# BB.net
KiCad netlist of a schematic drawn in Altium Designer
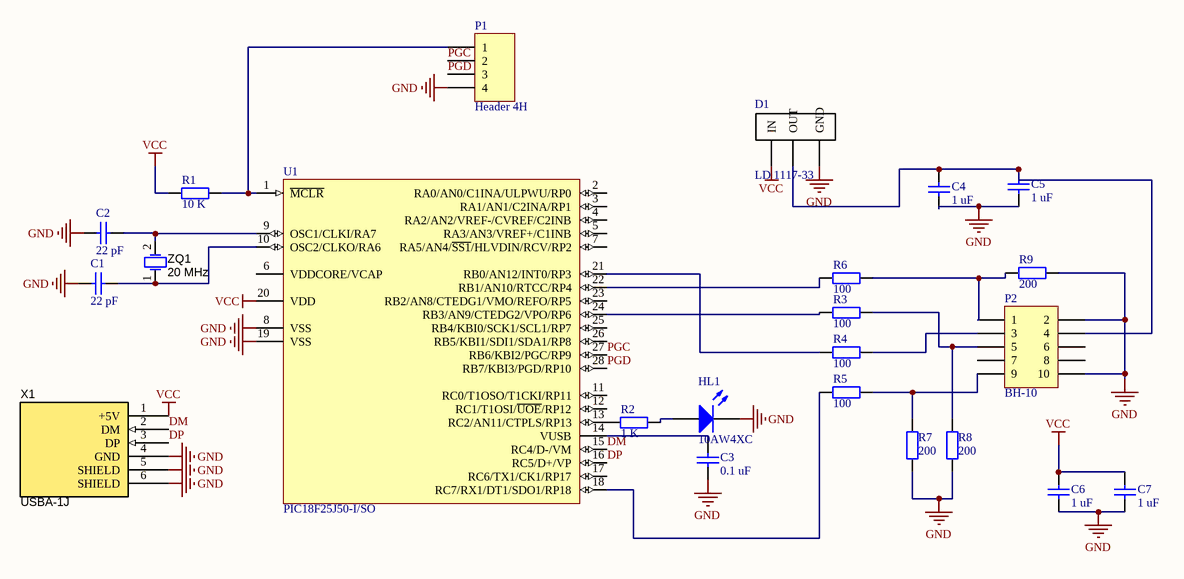
[diagram p0: BB.SchDoc]

(export (version "E")
  (design (tool "Eeschema 10.0.6"))
  (components
    (comp (ref "C1")
      (value "22 pF")
      (footprint "C0805")
      (description "Capacitor (Semiconductor SIM Model)")
      (fields (field (name "Comment") "Cap Semi_2") (field (name "PUBLISHER") "Sergeev"))
      (libsource (lib "Sergeev_altium_2012.03.10") (part "Cap Semi_2"))
    )
    (comp (ref "C2")
      (value "22 pF")
      (footprint "C0805")
      (description "Capacitor (Semiconductor SIM Model)")
      (fields (field (name "Comment") "Cap Semi_2") (field (name "PUBLISHER") "Sergeev"))
      (libsource (lib "Sergeev_altium_2012.03.10") (part "Cap Semi_2"))
    )
    (comp (ref "C3")
      (value "0.1 uF")
      (footprint "C0805")
      (description "Capacitor (Semiconductor SIM Model)")
      (fields (field (name "Comment") "Cap Semi_2") (field (name "PUBLISHER") "Sergeev"))
      (libsource (lib "Sergeev_altium_2012.03.10") (part "Cap Semi_2"))
    )
    (comp (ref "C4")
      (value "1 uF")
      (footprint "C0805")
      (description "Capacitor (Semiconductor SIM Model)")
      (fields (field (name "Comment") "Cap Semi_2") (field (name "PUBLISHER") "Sergeev"))
      (libsource (lib "Sergeev_altium_2012.03.10") (part "Cap Semi_2"))
    )
    (comp (ref "C5")
      (value "1 uF")
      (footprint "C0805")
      (description "Capacitor (Semiconductor SIM Model)")
      (fields (field (name "Comment") "Cap Semi_2") (field (name "PUBLISHER") "Sergeev"))
      (libsource (lib "Sergeev_altium_2012.03.10") (part "Cap Semi_2"))
    )
    (comp (ref "C6")
      (value "1 uF")
      (footprint "C0805")
      (description "Capacitor (Semiconductor SIM Model)")
      (fields (field (name "Comment") "Cap Semi_2") (field (name "PUBLISHER") "Sergeev"))
      (libsource (lib "Sergeev_altium_2012.03.10") (part "Cap Semi_2"))
    )
    (comp (ref "C7")
      (value "1 uF")
      (footprint "C0805")
      (description "Capacitor (Semiconductor SIM Model)")
      (fields (field (name "Comment") "Cap Semi_2") (field (name "PUBLISHER") "Sergeev"))
      (libsource (lib "Sergeev_altium_2012.03.10") (part "Cap Semi_2"))
    )
    (comp (ref "D1")
      (value "LD 1117-33")
      (footprint "SOT230P700X180-4N")
      (libsource (lib "BB") (part "LD 1117-33"))
    )
    (comp (ref "HL1")
      (value "10AW4XC")
      (footprint "Led_Rus D=10 d=0.9 w=2.54")
      (description "Typical INFRARED GaAs LED")
      (fields (field (name "PUBLISHER") "Сергеев"))
      (libsource (lib "Sergeev_altium_2012.03.10") (part "LED D=10"))
    )
    (comp (ref "P1")
      (value "Header 4H")
      (footprint "HDR1X4H")
      (description "Header, 4-Pin, Right Angle")
      (fields (field (name "PUBLISHER") "Altium Limited"))
      (libsource (lib "Miscellaneous Connectors") (part "Header 4H"))
    )
    (comp (ref "P2")
      (value "BH-10")
      (footprint "BH-10 HDR2X5")
      (description "Header, 5-Pin, Dual row 2.54")
      (fields (field (name "PUBLISHER") "Altium Limited"))
      (libsource (lib "Sergeev_altium_2012.03.10") (part "BH-10"))
    )
    (comp (ref "R1")
      (value "10 K")
      (footprint "2012[0805] - wa")
      (fields (field (name "Comment") "Resistor 0805"))
      (libsource (lib "Sergeev_altium_2012.03.10") (part "Resistor 0805"))
    )
    (comp (ref "R2")
      (value "1 K")
      (footprint "2012[0805] - wa")
      (fields (field (name "Comment") "Resistor 0805"))
      (libsource (lib "") (part "Resistor 0805_2"))
    )
    (comp (ref "R3")
      (value "100")
      (footprint "2012[0805] - wa")
      (fields (field (name "Comment") "Resistor 0805"))
      (libsource (lib "Sergeev_altium_2012.03.10") (part "Resistor 0805"))
    )
    (comp (ref "R4")
      (value "100")
      (footprint "2012[0805] - wa")
      (fields (field (name "Comment") "Resistor 0805"))
      (libsource (lib "Sergeev_altium_2012.03.10") (part "Resistor 0805"))
    )
    (comp (ref "R5")
      (value "100")
      (footprint "2012[0805] - wa")
      (fields (field (name "Comment") "Resistor 0805"))
      (libsource (lib "Sergeev_altium_2012.03.10") (part "Resistor 0805"))
    )
    (comp (ref "R6")
      (value "100")
      (footprint "2012[0805] - wa")
      (fields (field (name "Comment") "Resistor 0805"))
      (libsource (lib "Sergeev_altium_2012.03.10") (part "Resistor 0805"))
    )
    (comp (ref "R7")
      (value "200")
      (footprint "2012[0805] - wa")
      (fields (field (name "Comment") "Resistor 0805"))
      (libsource (lib "") (part "Resistor 0805_1"))
    )
    (comp (ref "R8")
      (value "200")
      (footprint "2012[0805] - wa")
      (fields (field (name "Comment") "Resistor 0805"))
      (libsource (lib "") (part "Resistor 0805_1"))
    )
    (comp (ref "R9")
      (value "200")
      (footprint "2012[0805] - wa")
      (fields (field (name "Comment") "Resistor 0805"))
      (libsource (lib "Sergeev_altium_2012.03.10") (part "Resistor 0805"))
    )
    (comp (ref "U1")
      (value "PIC18F25J50-I/SO")
      (footprint "SOIC-SO28_N")
      (fields (field (name "PUBLISHER") "Altium Limited"))
      (libsource (lib "Microchip Microcontroller 8-Bit PIC18") (part "PIC18F25J50-I/SO"))
    )
    (comp (ref "X1")
      (value "USBA-1J")
      (footprint "USB2.5-2H4C")
      (description "Разъем USBA на плату")
      (libsource (lib "Sergeev_altium_2012.03.10") (part "USBA-1J"))
    )
    (comp (ref "ZQ1")
      (value "20 MHz")
      (footprint "HC49S")
      (description "Crystal Oscillator")
      (fields (field (name "PUBLISHER") "Altium Limited"))
      (libsource (lib "Sergeev_altium_2012.03.10") (part "XTAL"))
    )
  )
  (nets
    (net (code "1") (name "/DM") (class "Default")
      (node (ref "U1") (pin "15") (pinfunction "RC4/D-/VM_15") (pintype "bidirectional"))
      (node (ref "X1") (pin "2") (pinfunction "DM_2") (pintype "input"))
    )
    (net (code "2") (name "/DP") (class "Default")
      (node (ref "U1") (pin "16") (pinfunction "RC5/D+/VP_16") (pintype "bidirectional"))
      (node (ref "X1") (pin "3") (pinfunction "DP_3") (pintype "input"))
    )
    (net (code "3") (name "/PGC") (class "Default")
      (node (ref "P1") (pin "2") (pinfunction "2_2") (pintype "passive"))
      (node (ref "U1") (pin "27") (pinfunction "RB6/KBI2/PGC/RP9_27") (pintype "bidirectional"))
    )
    (net (code "4") (name "/PGD") (class "Default")
      (node (ref "P1") (pin "3") (pinfunction "3_3") (pintype "passive"))
      (node (ref "U1") (pin "28") (pinfunction "RB7/KBI3/PGD/RP10_28") (pintype "bidirectional"))
    )
    (net (code "5") (name "GND") (class "Default")
      (node (ref "C1") (pin "2") (pinfunction "2_2") (pintype "passive"))
      (node (ref "C2") (pin "2") (pinfunction "2_2") (pintype "passive"))
      (node (ref "C3") (pin "1") (pinfunction "1_1") (pintype "passive"))
      (node (ref "C4") (pin "1") (pinfunction "1_1") (pintype "passive"))
      (node (ref "C5") (pin "1") (pinfunction "1_1") (pintype "passive"))
      (node (ref "C6") (pin "1") (pinfunction "1_1") (pintype "passive"))
      (node (ref "C7") (pin "1") (pinfunction "1_1") (pintype "passive"))
      (node (ref "D1") (pin "GND") (pinfunction "GND_GND") (pintype "passive"))
      (node (ref "HL1") (pin "2") (pinfunction "K_2") (pintype "passive"))
      (node (ref "P1") (pin "4") (pinfunction "4_4") (pintype "passive"))
      (node (ref "P2") (pin "10") (pinfunction "10_10") (pintype "passive"))
      (node (ref "P2") (pin "2") (pinfunction "2_2") (pintype "passive"))
      (node (ref "R7") (pin "1") (pinfunction "1_1") (pintype "passive"))
      (node (ref "R8") (pin "1") (pinfunction "1_1") (pintype "passive"))
      (node (ref "R9") (pin "2") (pinfunction "2_2") (pintype "passive"))
      (node (ref "U1") (pin "19") (pinfunction "VSS_19") (pintype "power_in"))
      (node (ref "U1") (pin "8") (pinfunction "VSS_8") (pintype "power_in"))
      (node (ref "X1") (pin "4") (pinfunction "GND_4") (pintype "power_in"))
      (node (ref "X1") (pin "5") (pinfunction "SHIELD_5") (pintype "power_in"))
      (node (ref "X1") (pin "6") (pinfunction "SHIELD_6") (pintype "power_in"))
    )
    (net (code "6") (name "Net-(C4-Pad2)") (class "Default")
      (node (ref "C4") (pin "2") (pinfunction "2_2") (pintype "passive"))
      (node (ref "C5") (pin "2") (pinfunction "2_2") (pintype "passive"))
      (node (ref "D1") (pin "OUT") (pinfunction "OUT_OUT") (pintype "passive"))
      (node (ref "P2") (pin "4") (pinfunction "4_4") (pintype "passive"))
    )
    (net (code "7") (name "Net-(HL1-A)") (class "Default")
      (node (ref "HL1") (pin "1") (pinfunction "A_1") (pintype "passive"))
      (node (ref "R2") (pin "1") (pinfunction "1_1") (pintype "passive"))
    )
    (net (code "8") (name "Net-(P2-Pad1)") (class "Default")
      (node (ref "P2") (pin "1") (pinfunction "1_1") (pintype "passive"))
      (node (ref "R6") (pin "2") (pinfunction "2_2") (pintype "passive"))
      (node (ref "R9") (pin "1") (pinfunction "1_1") (pintype "passive"))
    )
    (net (code "9") (name "Net-(P2-Pad3)") (class "Default")
      (node (ref "P2") (pin "3") (pinfunction "3_3") (pintype "passive"))
      (node (ref "R4") (pin "2") (pinfunction "2_2") (pintype "passive"))
    )
    (net (code "10") (name "Net-(P2-Pad5)") (class "Default")
      (node (ref "P2") (pin "5") (pinfunction "5_5") (pintype "passive"))
      (node (ref "R3") (pin "2") (pinfunction "2_2") (pintype "passive"))
      (node (ref "R8") (pin "2") (pinfunction "2_2") (pintype "passive"))
    )
    (net (code "11") (name "Net-(P2-Pad9)") (class "Default")
      (node (ref "P2") (pin "9") (pinfunction "9_9") (pintype "passive"))
      (node (ref "R5") (pin "2") (pinfunction "2_2") (pintype "passive"))
      (node (ref "R7") (pin "2") (pinfunction "2_2") (pintype "passive"))
    )
    (net (code "12") (name "Net-(U1-OSC1{slash}CLKI{slash}RA7)") (class "Default")
      (node (ref "C2") (pin "1") (pinfunction "1_1") (pintype "passive"))
      (node (ref "U1") (pin "9") (pinfunction "OSC1/CLKI/RA7_9") (pintype "bidirectional"))
      (node (ref "ZQ1") (pin "2") (pinfunction "OSC2_2") (pintype "passive"))
    )
    (net (code "13") (name "Net-(U1-OSC2{slash}CLKO{slash}RA6)") (class "Default")
      (node (ref "C1") (pin "1") (pinfunction "1_1") (pintype "passive"))
      (node (ref "U1") (pin "10") (pinfunction "OSC2/CLKO/RA6_10") (pintype "bidirectional"))
      (node (ref "ZQ1") (pin "1") (pinfunction "OSC1_1") (pintype "passive"))
    )
    (net (code "14") (name "Net-(U1-RB0{slash}AN12{slash}INT0{slash}RP3)") (class "Default")
      (node (ref "R4") (pin "1") (pinfunction "1_1") (pintype "passive"))
      (node (ref "U1") (pin "21") (pinfunction "RB0/AN12/INT0/RP3_21") (pintype "bidirectional"))
    )
    (net (code "15") (name "Net-(U1-RB1{slash}AN10{slash}RTCC{slash}RP4)") (class "Default")
      (node (ref "R6") (pin "1") (pinfunction "1_1") (pintype "passive"))
      (node (ref "U1") (pin "22") (pinfunction "RB1/AN10/RTCC/RP4_22") (pintype "bidirectional"))
    )
    (net (code "16") (name "Net-(U1-RB3{slash}AN9{slash}CTEDG2{slash}VPO{slash}RP6)") (class "Default")
      (node (ref "R3") (pin "1") (pinfunction "1_1") (pintype "passive"))
      (node (ref "U1") (pin "24") (pinfunction "RB3/AN9/CTEDG2/VPO/RP6_24") (pintype "bidirectional"))
    )
    (net (code "17") (name "Net-(U1-RC2{slash}AN11{slash}CTPLS{slash}RP13)") (class "Default")
      (node (ref "R2") (pin "2") (pinfunction "2_2") (pintype "passive"))
      (node (ref "U1") (pin "13") (pinfunction "RC2/AN11/CTPLS/RP13_13") (pintype "bidirectional"))
    )
    (net (code "18") (name "Net-(U1-RC7{slash}RX1{slash}DT1{slash}SDO1{slash}RP18)") (class "Default")
      (node (ref "R5") (pin "1") (pinfunction "1_1") (pintype "passive"))
      (node (ref "U1") (pin "18") (pinfunction "RC7/RX1/DT1/SDO1/RP18_18") (pintype "bidirectional"))
    )
    (net (code "19") (name "Net-(U1-VUSB)") (class "Default")
      (node (ref "C3") (pin "2") (pinfunction "2_2") (pintype "passive"))
      (node (ref "U1") (pin "14") (pinfunction "VUSB_14") (pintype "power_in"))
    )
    (net (code "20") (name "Net-(U1-~{MCLR})") (class "Default")
      (node (ref "P1") (pin "1") (pinfunction "1_1") (pintype "passive"))
      (node (ref "R1") (pin "2") (pinfunction "2_2") (pintype "passive"))
      (node (ref "U1") (pin "1") (pinfunction "~{MCLR}_1") (pintype "input"))
    )
    (net (code "21") (name "VCC") (class "Default")
      (node (ref "C6") (pin "2") (pinfunction "2_2") (pintype "passive"))
      (node (ref "C7") (pin "2") (pinfunction "2_2") (pintype "passive"))
      (node (ref "D1") (pin "IN") (pinfunction "IN_IN") (pintype "passive"))
      (node (ref "R1") (pin "1") (pinfunction "1_1") (pintype "passive"))
      (node (ref "U1") (pin "20") (pinfunction "VDD_20") (pintype "power_in"))
      (node (ref "X1") (pin "1") (pinfunction "+5V_1") (pintype "power_in"))
    )
    (net (code "22") (name "unconnected-(P2-Pad6)") (class "Default")
      (node (ref "P2") (pin "6") (pinfunction "6_6") (pintype "passive"))
    )
    (net (code "23") (name "unconnected-(P2-Pad7)") (class "Default")
      (node (ref "P2") (pin "7") (pinfunction "7_7") (pintype "passive"))
    )
    (net (code "24") (name "unconnected-(P2-Pad8)") (class "Default")
      (node (ref "P2") (pin "8") (pinfunction "8_8") (pintype "passive"))
    )
    (net (code "25") (name "unconnected-(U1-RA0{slash}AN0{slash}C1INA{slash}ULPWU{slash}RP0-Pad2)") (class "Default")
      (node (ref "U1") (pin "2") (pinfunction "RA0/AN0/C1INA/ULPWU/RP0_2") (pintype "bidirectional"))
    )
    (net (code "26") (name "unconnected-(U1-RA1{slash}AN1{slash}C2INA{slash}RP1-Pad3)") (class "Default")
      (node (ref "U1") (pin "3") (pinfunction "RA1/AN1/C2INA/RP1_3") (pintype "bidirectional"))
    )
    (net (code "27") (name "unconnected-(U1-RA2{slash}AN2{slash}VREF-{slash}CVREF{slash}C2INB-Pad4)") (class "Default")
      (node (ref "U1") (pin "4") (pinfunction "RA2/AN2/VREF-/CVREF/C2INB_4") (pintype "bidirectional"))
    )
    (net (code "28") (name "unconnected-(U1-RA3{slash}AN3{slash}VREF+{slash}C1INB-Pad5)") (class "Default")
      (node (ref "U1") (pin "5") (pinfunction "RA3/AN3/VREF+/C1INB_5") (pintype "bidirectional"))
    )
    (net (code "29") (name "unconnected-(U1-RA5{slash}AN4{slash}~{SS1}{slash}HLVDIN{slash}RCV{slash}RP2-Pad7)") (class "Default")
      (node (ref "U1") (pin "7") (pinfunction "RA5/AN4/~{SS1}/HLVDIN/RCV/RP2_7") (pintype "bidirectional"))
    )
    (net (code "30") (name "unconnected-(U1-RB2{slash}AN8{slash}CTEDG1{slash}VMO{slash}REFO{slash}RP5-Pad23)") (class "Default")
      (node (ref "U1") (pin "23") (pinfunction "RB2/AN8/CTEDG1/VMO/REFO/RP5_23") (pintype "bidirectional"))
    )
    (net (code "31") (name "unconnected-(U1-RB4{slash}KBI0{slash}SCK1{slash}SCL1{slash}RP7-Pad25)") (class "Default")
      (node (ref "U1") (pin "25") (pinfunction "RB4/KBI0/SCK1/SCL1/RP7_25") (pintype "bidirectional"))
    )
    (net (code "32") (name "unconnected-(U1-RB5{slash}KBI1{slash}SDI1{slash}SDA1{slash}RP8-Pad26)") (class "Default")
      (node (ref "U1") (pin "26") (pinfunction "RB5/KBI1/SDI1/SDA1/RP8_26") (pintype "bidirectional"))
    )
    (net (code "33") (name "unconnected-(U1-RC0{slash}T1OSO{slash}T1CKI{slash}RP11-Pad11)") (class "Default")
      (node (ref "U1") (pin "11") (pinfunction "RC0/T1OSO/T1CKI/RP11_11") (pintype "bidirectional"))
    )
    (net (code "34") (name "unconnected-(U1-RC1{slash}T1OSI{slash}~{UOE}{slash}RP12-Pad12)") (class "Default")
      (node (ref "U1") (pin "12") (pinfunction "RC1/T1OSI/~{UOE}/RP12_12") (pintype "bidirectional"))
    )
    (net (code "35") (name "unconnected-(U1-RC6{slash}TX1{slash}CK1{slash}RP17-Pad17)") (class "Default")
      (node (ref "U1") (pin "17") (pinfunction "RC6/TX1/CK1/RP17_17") (pintype "bidirectional"))
    )
    (net (code "36") (name "unconnected-(U1-VDDCORE{slash}VCAP-Pad6)") (class "Default")
      (node (ref "U1") (pin "6") (pinfunction "VDDCORE/VCAP_6") (pintype "power_in"))
    )
  )
)
